# Sample_Holder_DC_Small.net
KiCad netlist of a schematic drawn in Altium Designer
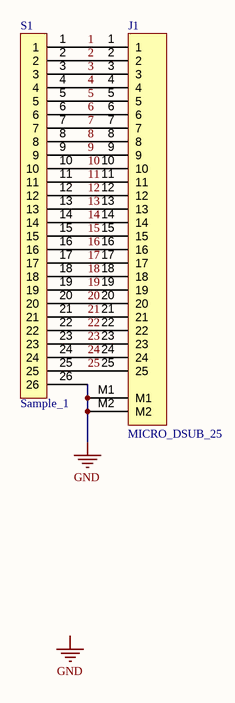
[diagram p0: Sample_Holder_DC_Small.SchDoc]

(export (version "E")
  (design (tool "Eeschema 10.0.6"))
  (components
    (comp (ref "J1")
      (value "MICRO_DSUB_25")
      (footprint "581-M25-113L461")
      (description "Micro D-Sub 25 pin connector")
      (libsource (lib "Connectors") (part "MICRO_DSUB_25"))
    )
    (comp (ref "S1") (value "Sample_1") (footprint "Sample_1") (libsource (lib "Samples") (part "Sample_1")))
  )
  (nets
    (net (code "1") (name "/1") (class "Default")
      (node (ref "J1") (pin "1") (pinfunction "1_1") (pintype "passive"))
      (node (ref "S1") (pin "1") (pinfunction "1_1") (pintype "passive"))
    )
    (net (code "2") (name "/2") (class "Default")
      (node (ref "J1") (pin "2") (pinfunction "2_2") (pintype "passive"))
      (node (ref "S1") (pin "2") (pinfunction "2_2") (pintype "passive"))
    )
    (net (code "3") (name "/3") (class "Default")
      (node (ref "J1") (pin "3") (pinfunction "3_3") (pintype "passive"))
      (node (ref "S1") (pin "3") (pinfunction "3_3") (pintype "passive"))
    )
    (net (code "4") (name "/4") (class "Default")
      (node (ref "J1") (pin "4") (pinfunction "4_4") (pintype "passive"))
      (node (ref "S1") (pin "4") (pinfunction "4_4") (pintype "passive"))
    )
    (net (code "5") (name "/5") (class "Default")
      (node (ref "J1") (pin "5") (pinfunction "5_5") (pintype "passive"))
      (node (ref "S1") (pin "5") (pinfunction "5_5") (pintype "passive"))
    )
    (net (code "6") (name "/6") (class "Default")
      (node (ref "J1") (pin "6") (pinfunction "6_6") (pintype "passive"))
      (node (ref "S1") (pin "6") (pinfunction "6_6") (pintype "passive"))
    )
    (net (code "7") (name "/7") (class "Default")
      (node (ref "J1") (pin "7") (pinfunction "7_7") (pintype "passive"))
      (node (ref "S1") (pin "7") (pinfunction "7_7") (pintype "passive"))
    )
    (net (code "8") (name "/8") (class "Default")
      (node (ref "J1") (pin "8") (pinfunction "8_8") (pintype "passive"))
      (node (ref "S1") (pin "8") (pinfunction "8_8") (pintype "passive"))
    )
    (net (code "9") (name "/9") (class "Default")
      (node (ref "J1") (pin "9") (pinfunction "9_9") (pintype "passive"))
      (node (ref "S1") (pin "9") (pinfunction "9_9") (pintype "passive"))
    )
    (net (code "10") (name "/10") (class "Default")
      (node (ref "J1") (pin "10") (pinfunction "10_10") (pintype "passive"))
      (node (ref "S1") (pin "10") (pinfunction "10_10") (pintype "passive"))
    )
    (net (code "11") (name "/11") (class "Default")
      (node (ref "J1") (pin "11") (pinfunction "11_11") (pintype "passive"))
      (node (ref "S1") (pin "11") (pinfunction "11_11") (pintype "passive"))
    )
    (net (code "12") (name "/12") (class "Default")
      (node (ref "J1") (pin "12") (pinfunction "12_12") (pintype "passive"))
      (node (ref "S1") (pin "12") (pinfunction "12_12") (pintype "passive"))
    )
    (net (code "13") (name "/13") (class "Default")
      (node (ref "J1") (pin "13") (pinfunction "13_13") (pintype "passive"))
      (node (ref "S1") (pin "13") (pinfunction "13_13") (pintype "passive"))
    )
    (net (code "14") (name "/14") (class "Default")
      (node (ref "J1") (pin "14") (pinfunction "14_14") (pintype "passive"))
      (node (ref "S1") (pin "14") (pinfunction "14_14") (pintype "passive"))
    )
    (net (code "15") (name "/15") (class "Default")
      (node (ref "J1") (pin "15") (pinfunction "15_15") (pintype "passive"))
      (node (ref "S1") (pin "15") (pinfunction "15_15") (pintype "passive"))
    )
    (net (code "16") (name "/16") (class "Default")
      (node (ref "J1") (pin "16") (pinfunction "16_16") (pintype "passive"))
      (node (ref "S1") (pin "16") (pinfunction "16_16") (pintype "passive"))
    )
    (net (code "17") (name "/17") (class "Default")
      (node (ref "J1") (pin "17") (pinfunction "17_17") (pintype "passive"))
      (node (ref "S1") (pin "17") (pinfunction "17_17") (pintype "passive"))
    )
    (net (code "18") (name "/18") (class "Default")
      (node (ref "J1") (pin "18") (pinfunction "18_18") (pintype "passive"))
      (node (ref "S1") (pin "18") (pinfunction "18_18") (pintype "passive"))
    )
    (net (code "19") (name "/19") (class "Default")
      (node (ref "J1") (pin "19") (pinfunction "19_19") (pintype "passive"))
      (node (ref "S1") (pin "19") (pinfunction "19_19") (pintype "passive"))
    )
    (net (code "20") (name "/20") (class "Default")
      (node (ref "J1") (pin "20") (pinfunction "20_20") (pintype "passive"))
      (node (ref "S1") (pin "20") (pinfunction "20_20") (pintype "passive"))
    )
    (net (code "21") (name "/21") (class "Default")
      (node (ref "J1") (pin "21") (pinfunction "21_21") (pintype "passive"))
      (node (ref "S1") (pin "21") (pinfunction "21_21") (pintype "passive"))
    )
    (net (code "22") (name "/22") (class "Default")
      (node (ref "J1") (pin "22") (pinfunction "22_22") (pintype "passive"))
      (node (ref "S1") (pin "22") (pinfunction "22_22") (pintype "passive"))
    )
    (net (code "23") (name "/23") (class "Default")
      (node (ref "J1") (pin "23") (pinfunction "23_23") (pintype "passive"))
      (node (ref "S1") (pin "23") (pinfunction "23_23") (pintype "passive"))
    )
    (net (code "24") (name "/24") (class "Default")
      (node (ref "J1") (pin "24") (pinfunction "24_24") (pintype "passive"))
      (node (ref "S1") (pin "24") (pinfunction "24_24") (pintype "passive"))
    )
    (net (code "25") (name "/25") (class "Default")
      (node (ref "J1") (pin "25") (pinfunction "25_25") (pintype "passive"))
      (node (ref "S1") (pin "25") (pinfunction "25_25") (pintype "passive"))
    )
    (net (code "26") (name "GND") (class "Default")
      (node (ref "J1") (pin "M1") (pinfunction "M1_M1") (pintype "passive"))
      (node (ref "J1") (pin "M2") (pinfunction "M2_M2") (pintype "passive"))
      (node (ref "S1") (pin "26") (pinfunction "26_26") (pintype "passive"))
    )
  )
)
